# BMI270-SensorBoard.net
KiCad netlist of a schematic drawn in EAGLE
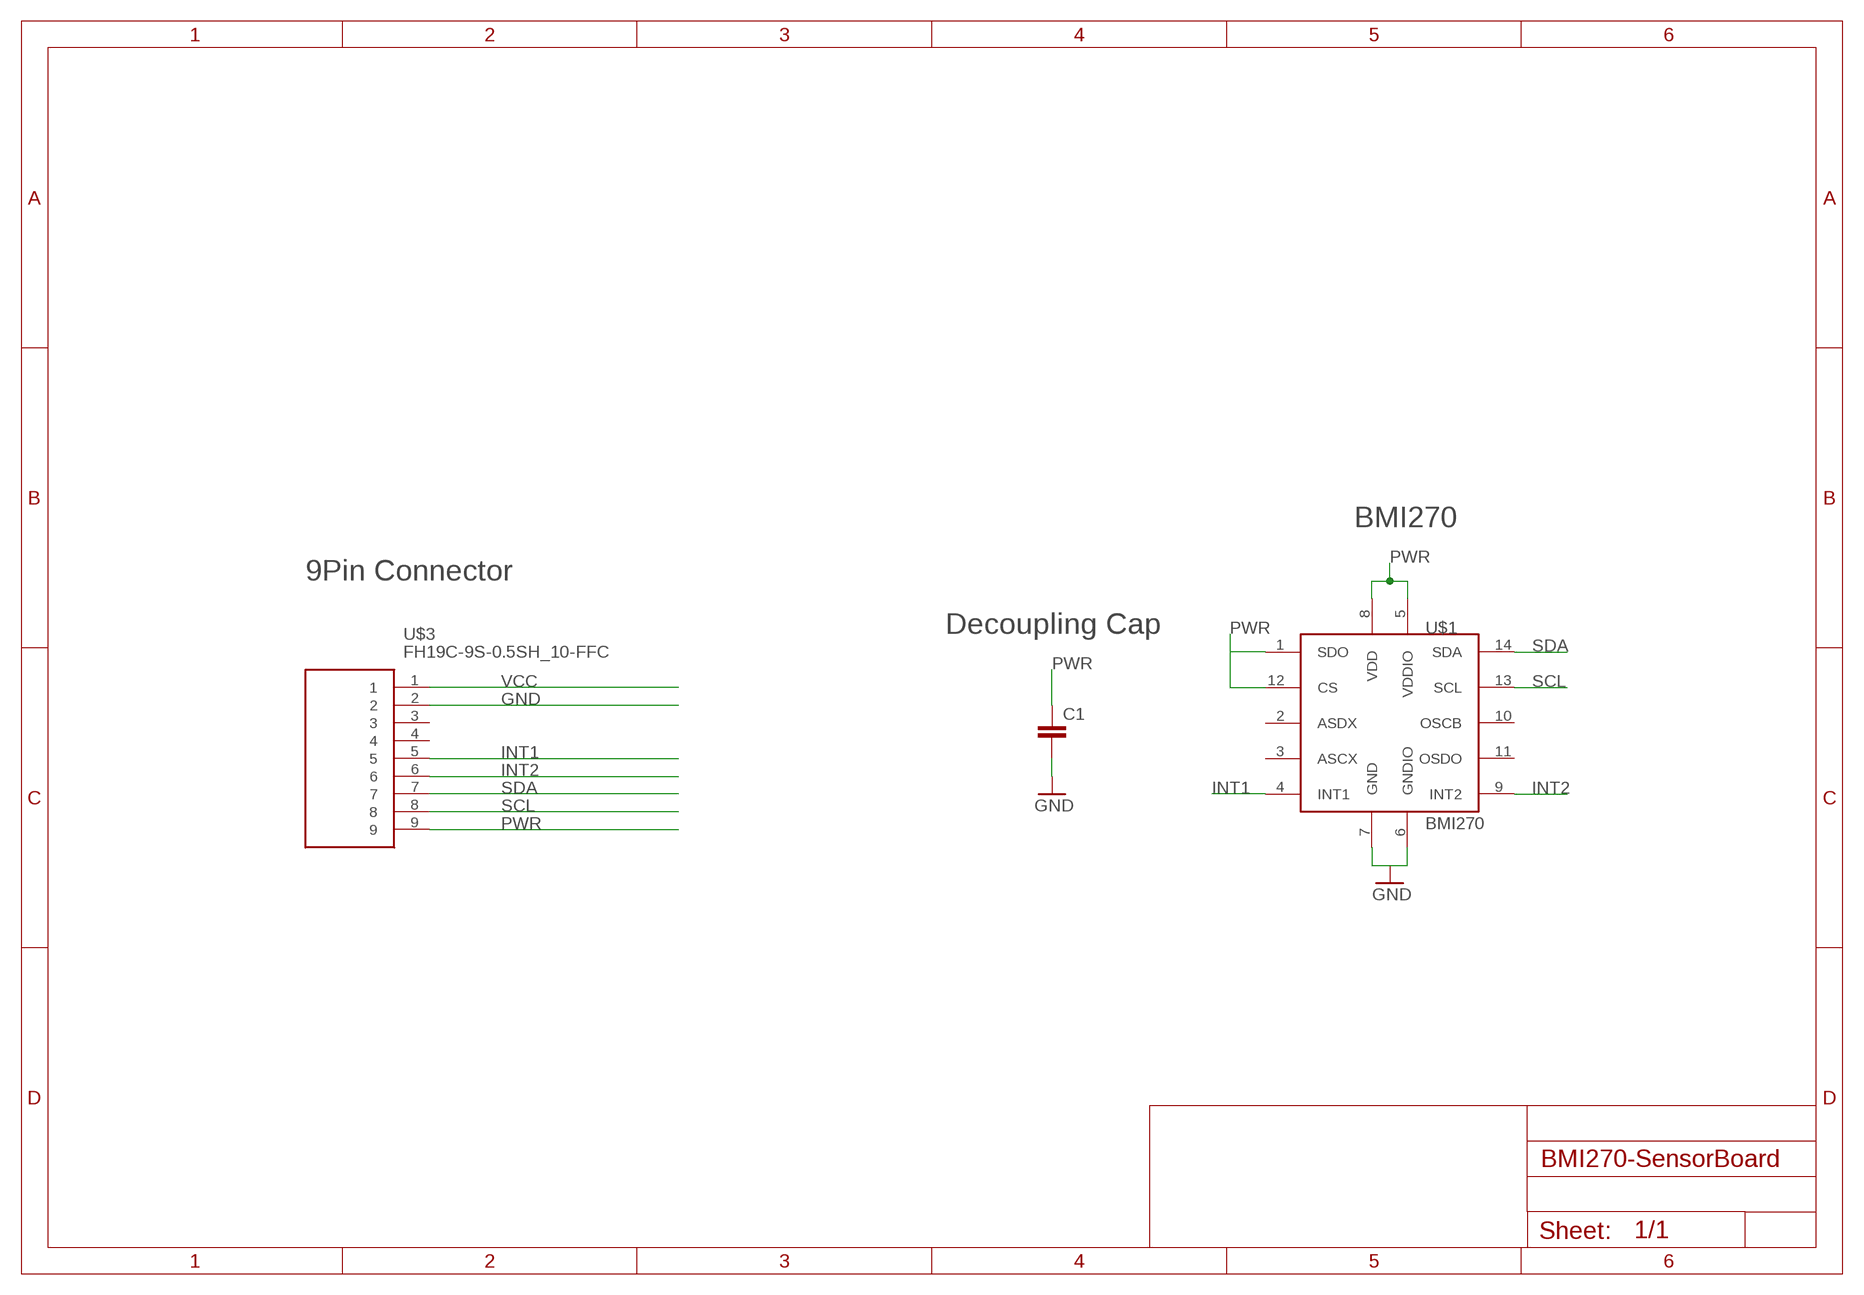
[diagram p0: schematic, sheet 1]

(export (version "E")
  (design (tool "Eeschema 10.0.6"))
  (components
    (comp (ref "C1")
      (value "C-EUC0603K")
      (footprint "eagle-import:C0603K")
      (libsource (lib "eagle-import") (part "C-EUC0603K"))
    )
    (comp (ref "U$1")
      (value "BMI270")
      (footprint "eagle-import:XDCR_BMI270")
      (libsource (lib "eagle-import") (part "BMI270"))
    )
    (comp (ref "U$3")
      (value "FH19C-9S-0.5SH_10-FFC")
      (footprint "eagle-import:FH19C9S05SH10-FFC")
      (libsource (lib "eagle-import") (part "FH19C-9S-0.5SH_10-FFC"))
    )
  )
  (nets
    (net (code "1") (name "/INT1") (class "Default")
      (node (ref "U$1") (pin "4") (pinfunction "INT1_4") (pintype "bidirectional"))
      (node (ref "U$3") (pin "5") (pinfunction "5_5") (pintype "bidirectional"))
    )
    (net (code "2") (name "/INT2") (class "Default")
      (node (ref "U$1") (pin "9") (pinfunction "INT2_9") (pintype "bidirectional"))
      (node (ref "U$3") (pin "6") (pinfunction "6_6") (pintype "bidirectional"))
    )
    (net (code "3") (name "/PWR") (class "Default")
      (node (ref "C1") (pin "1") (pinfunction "1_1") (pintype "passive"))
      (node (ref "U$1") (pin "1") (pinfunction "SDO_1") (pintype "bidirectional"))
      (node (ref "U$1") (pin "12") (pinfunction "CS_12") (pintype "bidirectional"))
      (node (ref "U$1") (pin "5") (pinfunction "VDDIO_5") (pintype "bidirectional"))
      (node (ref "U$1") (pin "8") (pinfunction "VDD_8") (pintype "bidirectional"))
      (node (ref "U$3") (pin "9") (pinfunction "9_9") (pintype "bidirectional"))
    )
    (net (code "4") (name "/SCL") (class "Default")
      (node (ref "U$1") (pin "13") (pinfunction "SCL_13") (pintype "bidirectional"))
      (node (ref "U$3") (pin "8") (pinfunction "8_8") (pintype "bidirectional"))
    )
    (net (code "5") (name "/SDA") (class "Default")
      (node (ref "U$1") (pin "14") (pinfunction "SDA_14") (pintype "bidirectional"))
      (node (ref "U$3") (pin "7") (pinfunction "7_7") (pintype "bidirectional"))
    )
    (net (code "6") (name "/VCC") (class "Default")
      (node (ref "U$3") (pin "1") (pinfunction "1_1") (pintype "bidirectional"))
    )
    (net (code "7") (name "GND") (class "Default")
      (node (ref "C1") (pin "2") (pinfunction "2_2") (pintype "passive"))
      (node (ref "U$1") (pin "6") (pinfunction "GNDIO_6") (pintype "bidirectional"))
      (node (ref "U$1") (pin "7") (pinfunction "GND_7") (pintype "bidirectional"))
      (node (ref "U$3") (pin "2") (pinfunction "2_2") (pintype "bidirectional"))
    )
    (net (code "8") (name "unconnected-(U$1-ASCX-Pad3)") (class "Default")
      (node (ref "U$1") (pin "3") (pinfunction "ASCX_3") (pintype "bidirectional"))
    )
    (net (code "9") (name "unconnected-(U$1-ASDX-Pad2)") (class "Default")
      (node (ref "U$1") (pin "2") (pinfunction "ASDX_2") (pintype "bidirectional"))
    )
    (net (code "10") (name "unconnected-(U$1-OSCB-Pad10)") (class "Default")
      (node (ref "U$1") (pin "10") (pinfunction "OSCB_10") (pintype "bidirectional"))
    )
    (net (code "11") (name "unconnected-(U$1-OSDO-Pad11)") (class "Default")
      (node (ref "U$1") (pin "11") (pinfunction "OSDO_11") (pintype "bidirectional"))
    )
    (net (code "12") (name "unconnected-(U$3-Pad3)") (class "Default")
      (node (ref "U$3") (pin "3") (pinfunction "3_3") (pintype "bidirectional"))
    )
    (net (code "13") (name "unconnected-(U$3-Pad4)") (class "Default")
      (node (ref "U$3") (pin "4") (pinfunction "4_4") (pintype "bidirectional"))
    )
  )
)
